# I2C_Protection.net
KiCad netlist of a schematic drawn in Altium Designer
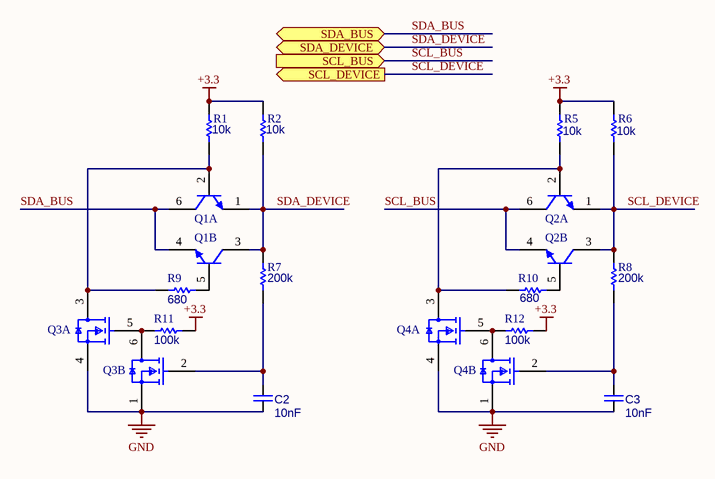
[diagram p0: I2C_Protection.SchDoc]

(export (version "E")
  (design (tool "Eeschema 10.0.6"))
  (components
    (comp (ref "C2")
      (value "10nF")
      (footprint "C0805A")
      (description "Non-polarized capacitor")
      (fields (field (name "Comment") "Capacitor"))
      (libsource (lib "Space Concordia") (part "Capacitor"))
    )
    (comp (ref "C3")
      (value "10nF")
      (footprint "C0805A")
      (description "Non-polarized capacitor")
      (fields (field (name "Comment") "Capacitor"))
      (libsource (lib "Space Concordia") (part "Capacitor"))
    )
    (comp (ref "Q1")
      (value "MBT2222ADW1T1")
      (footprint "ONSC-SOT-363-6-419B-02_V")
      (description "Small Signal Bipolar Transistor")
      (libsource (lib "Space Concordia") (part "ONSC-NPN_NPN-6_F"))
    )
    (comp (ref "Q2")
      (value "MBT2222ADW1T1")
      (footprint "ONSC-SOT-363-6-419B-02_V")
      (description "Small Signal Bipolar Transistor")
      (libsource (lib "Space Concordia") (part "ONSC-NPN_NPN-6_F"))
    )
    (comp (ref "Q3")
      (value "BSS138DW-7-F")
      (footprint "FP-SOT363-IPC_C")
      (description "Dual N-Channel 50 V 3.5 Ohm Surface Mount Enhancement MosFet - SOT-363")
      (libsource (lib "Space Concordia") (part "297539c3904897ba936602102abf918"))
    )
    (comp (ref "Q4")
      (value "BSS138DW-7-F")
      (footprint "FP-SOT363-IPC_C")
      (description "Dual N-Channel 50 V 3.5 Ohm Surface Mount Enhancement MosFet - SOT-363")
      (libsource (lib "Space Concordia") (part "297539c3904897ba936602102abf918"))
    )
    (comp (ref "R1")
      (value "10k")
      (footprint "R0603A")
      (description "Resistor")
      (libsource (lib "Space Concordia") (part "Resistor"))
    )
    (comp (ref "R2")
      (value "10k")
      (footprint "R0603A")
      (description "Resistor")
      (libsource (lib "Space Concordia") (part "Resistor"))
    )
    (comp (ref "R5")
      (value "10k")
      (footprint "R0603A")
      (description "Resistor")
      (libsource (lib "Space Concordia") (part "Resistor"))
    )
    (comp (ref "R6")
      (value "10k")
      (footprint "R0603A")
      (description "Resistor")
      (libsource (lib "Space Concordia") (part "Resistor"))
    )
    (comp (ref "R7")
      (value "200k")
      (footprint "R0603A")
      (description "Resistor")
      (fields (field (name "Comment") "RMCF0603FT200K"))
      (libsource (lib "Space Concordia") (part "Resistor"))
    )
    (comp (ref "R8")
      (value "200k")
      (footprint "R0603A")
      (description "Resistor")
      (fields (field (name "Comment") "RMCF0603FT200K"))
      (libsource (lib "Space Concordia") (part "Resistor"))
    )
    (comp (ref "R9")
      (value "680")
      (footprint "R0603A")
      (description "Resistor")
      (fields (field (name "Comment") "RMCF0603FT680R"))
      (libsource (lib "Space Concordia") (part "Resistor"))
    )
    (comp (ref "R10")
      (value "680")
      (footprint "R0603A")
      (description "Resistor")
      (fields (field (name "Comment") "RMCF0603FT680R"))
      (libsource (lib "Space Concordia") (part "Resistor"))
    )
    (comp (ref "R11")
      (value "100k")
      (footprint "R0603A")
      (description "Resistor")
      (fields (field (name "Comment") "RMCF0603JT100K"))
      (libsource (lib "Space Concordia") (part "Resistor"))
    )
    (comp (ref "R12")
      (value "100k")
      (footprint "R0603A")
      (description "Resistor")
      (fields (field (name "Comment") "RMCF0603JT100K"))
      (libsource (lib "Space Concordia") (part "Resistor"))
    )
  )
  (nets
    (net (code "1") (name "+3.3") (class "Default")
      (node (ref "R1") (pin "2") (pinfunction "2_2") (pintype "passive"))
      (node (ref "R11") (pin "1") (pinfunction "1_1") (pintype "passive"))
      (node (ref "R12") (pin "1") (pinfunction "1_1") (pintype "passive"))
      (node (ref "R2") (pin "2") (pinfunction "2_2") (pintype "passive"))
      (node (ref "R5") (pin "2") (pinfunction "2_2") (pintype "passive"))
      (node (ref "R6") (pin "2") (pinfunction "2_2") (pintype "passive"))
    )
    (net (code "2") (name "/SCL_BUS") (class "Default")
      (node (ref "Q2") (pin "4") (pinfunction "E_4") (pintype "passive"))
      (node (ref "Q2") (pin "6") (pinfunction "C_6") (pintype "passive"))
    )
    (net (code "3") (name "/SCL_DEVICE") (class "Default")
      (node (ref "Q2") (pin "1") (pinfunction "E_1") (pintype "passive"))
      (node (ref "Q2") (pin "3") (pinfunction "C_3") (pintype "passive"))
      (node (ref "R6") (pin "1") (pinfunction "1_1") (pintype "passive"))
      (node (ref "R8") (pin "2") (pinfunction "2_2") (pintype "passive"))
    )
    (net (code "4") (name "/SDA_BUS") (class "Default")
      (node (ref "Q1") (pin "4") (pinfunction "E_4") (pintype "passive"))
      (node (ref "Q1") (pin "6") (pinfunction "C_6") (pintype "passive"))
    )
    (net (code "5") (name "/SDA_DEVICE") (class "Default")
      (node (ref "Q1") (pin "1") (pinfunction "E_1") (pintype "passive"))
      (node (ref "Q1") (pin "3") (pinfunction "C_3") (pintype "passive"))
      (node (ref "R2") (pin "1") (pinfunction "1_1") (pintype "passive"))
      (node (ref "R7") (pin "2") (pinfunction "2_2") (pintype "passive"))
    )
    (net (code "6") (name "GND") (class "Default")
      (node (ref "C2") (pin "1") (pinfunction "1_1") (pintype "passive"))
      (node (ref "C3") (pin "1") (pinfunction "1_1") (pintype "passive"))
      (node (ref "Q3") (pin "1") (pinfunction "S2_1") (pintype "passive"))
      (node (ref "Q3") (pin "4") (pinfunction "S1_4") (pintype "passive"))
      (node (ref "Q4") (pin "1") (pinfunction "S2_1") (pintype "passive"))
      (node (ref "Q4") (pin "4") (pinfunction "S1_4") (pintype "passive"))
    )
    (net (code "7") (name "Net-(Q1A-B)") (class "Default")
      (node (ref "Q1") (pin "2") (pinfunction "B_2") (pintype "passive"))
      (node (ref "Q3") (pin "3") (pinfunction "D1_3") (pintype "passive"))
      (node (ref "R1") (pin "1") (pinfunction "1_1") (pintype "passive"))
      (node (ref "R9") (pin "1") (pinfunction "1_1") (pintype "passive"))
    )
    (net (code "8") (name "Net-(Q1B-B)") (class "Default")
      (node (ref "Q1") (pin "5") (pinfunction "B_5") (pintype "passive"))
      (node (ref "R9") (pin "2") (pinfunction "2_2") (pintype "passive"))
    )
    (net (code "9") (name "Net-(Q2A-B)") (class "Default")
      (node (ref "Q2") (pin "2") (pinfunction "B_2") (pintype "passive"))
      (node (ref "Q4") (pin "3") (pinfunction "D1_3") (pintype "passive"))
      (node (ref "R10") (pin "1") (pinfunction "1_1") (pintype "passive"))
      (node (ref "R5") (pin "1") (pinfunction "1_1") (pintype "passive"))
    )
    (net (code "10") (name "Net-(Q2B-B)") (class "Default")
      (node (ref "Q2") (pin "5") (pinfunction "B_5") (pintype "passive"))
      (node (ref "R10") (pin "2") (pinfunction "2_2") (pintype "passive"))
    )
    (net (code "11") (name "Net-(Q3A-G1)") (class "Default")
      (node (ref "Q3") (pin "5") (pinfunction "G1_5") (pintype "passive"))
      (node (ref "Q3") (pin "6") (pinfunction "D2_6") (pintype "passive"))
      (node (ref "R11") (pin "2") (pinfunction "2_2") (pintype "passive"))
    )
    (net (code "12") (name "Net-(Q3B-G2)") (class "Default")
      (node (ref "C2") (pin "2") (pinfunction "2_2") (pintype "passive"))
      (node (ref "Q3") (pin "2") (pinfunction "G2_2") (pintype "passive"))
      (node (ref "R7") (pin "1") (pinfunction "1_1") (pintype "passive"))
    )
    (net (code "13") (name "Net-(Q4A-G1)") (class "Default")
      (node (ref "Q4") (pin "5") (pinfunction "G1_5") (pintype "passive"))
      (node (ref "Q4") (pin "6") (pinfunction "D2_6") (pintype "passive"))
      (node (ref "R12") (pin "2") (pinfunction "2_2") (pintype "passive"))
    )
    (net (code "14") (name "Net-(Q4B-G2)") (class "Default")
      (node (ref "C3") (pin "2") (pinfunction "2_2") (pintype "passive"))
      (node (ref "Q4") (pin "2") (pinfunction "G2_2") (pintype "passive"))
      (node (ref "R8") (pin "1") (pinfunction "1_1") (pintype "passive"))
    )
  )
)
